# RGB_Video_Controller.net
KiCad netlist of a schematic drawn in Altium Designer
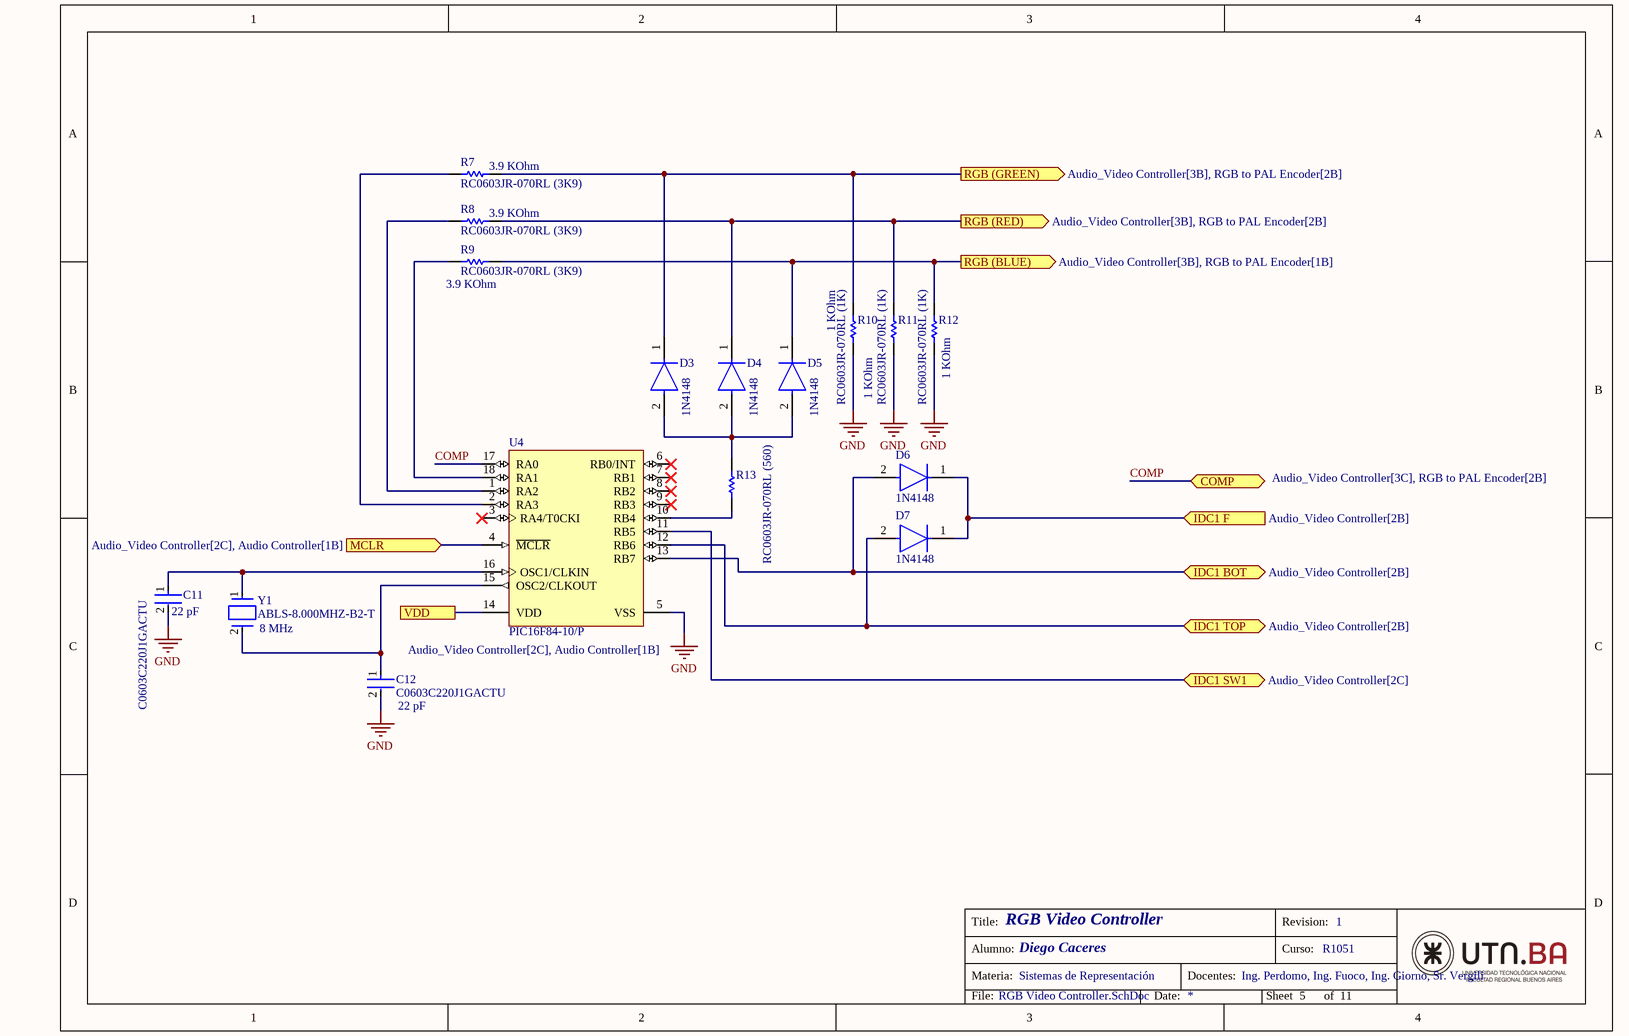
[diagram p0: RGB Video Controller.SchDoc]

(export (version "E")
  (design (tool "Eeschema 10.0.6"))
  (components
    (comp (ref "C11")
      (value "C0603C220J1GACTU")
      (footprint "FP-C0603C-CF-MFG")
      (description "CAP CER 22PF 100V 5% NP0 0603")
      (fields
        (field (name "ALTIUM_VALUE") "22 pF")
        (field (name "MANUFACTURER") "KEMET")
        (field (name "TOLERANCE") "0.05")
      )
      (libsource (lib "Altium Content Vault") (part "b4654b650e69147ec39a6b967a45e02"))
    )
    (comp (ref "C12")
      (value "C0603C220J1GACTU")
      (footprint "FP-C0603C-CF-MFG")
      (description "CAP CER 22PF 100V 5% NP0 0603")
      (fields
        (field (name "ALTIUM_VALUE") "22 pF")
        (field (name "MANUFACTURER") "KEMET")
        (field (name "TOLERANCE") "0.05")
      )
      (libsource (lib "Altium Content Vault") (part "b4654b650e69147ec39a6b967a45e02"))
    )
    (comp (ref "D3")
      (value "1N4148")
      (footprint "FP-017AG-MFG")
      (description "DIODE GEN PURP 100V 200MA DO35")
      (fields (field (name "VOLTAGE") "100V"))
      (libsource (lib "Altium Content Vault") (part "d7152d700b627762746794eb795d46e"))
    )
    (comp (ref "D4")
      (value "1N4148")
      (footprint "FP-017AG-MFG")
      (description "DIODE GEN PURP 100V 200MA DO35")
      (fields (field (name "VOLTAGE") "100V"))
      (libsource (lib "Altium Content Vault") (part "d7152d700b627762746794eb795d46e"))
    )
    (comp (ref "D5")
      (value "1N4148")
      (footprint "FP-017AG-MFG")
      (description "DIODE GEN PURP 100V 200MA DO35")
      (fields (field (name "VOLTAGE") "100V"))
      (libsource (lib "Altium Content Vault") (part "d7152d700b627762746794eb795d46e"))
    )
    (comp (ref "D6")
      (value "1N4148")
      (footprint "FP-017AG-MFG")
      (description "DIODE GEN PURP 100V 200MA DO35")
      (fields (field (name "VOLTAGE") "100V"))
      (libsource (lib "Altium Content Vault") (part "d7152d700b627762746794eb795d46e"))
    )
    (comp (ref "D7")
      (value "1N4148")
      (footprint "FP-017AG-MFG")
      (description "DIODE GEN PURP 100V 200MA DO35")
      (fields (field (name "VOLTAGE") "100V"))
      (libsource (lib "Altium Content Vault") (part "d7152d700b627762746794eb795d46e"))
    )
    (comp (ref "R7")
      (value "RC0603JR-070RL (3K9)")
      (footprint "RESC1608X55X25ML10T15")
      (description "Chip Resistor, 0 Ohm, +/- 5%, 0.1 W, -55 to 155 degC, 0603 (1608 Metric), RoHS, Tape and Reel")
      (fields
        (field (name "TOLERANCE") "5%")
        (field (name "RESISTANCE") "3.9 KOhm")
        (field (name "MANUFACTURER") "Yageo")
      )
      (libsource (lib "Altium Content Vault") (part "RES-2"))
    )
    (comp (ref "R8")
      (value "RC0603JR-070RL (3K9)")
      (footprint "RESC1608X55X25ML10T15")
      (description "Chip Resistor, 0 Ohm, +/- 5%, 0.1 W, -55 to 155 degC, 0603 (1608 Metric), RoHS, Tape and Reel")
      (fields
        (field (name "TOLERANCE") "5%")
        (field (name "RESISTANCE") "3.9 KOhm")
        (field (name "MANUFACTURER") "Yageo")
      )
      (libsource (lib "Altium Content Vault") (part "RES-2"))
    )
    (comp (ref "R9")
      (value "RC0603JR-070RL (3K9)")
      (footprint "RESC1608X55X25ML10T15")
      (description "Chip Resistor, 0 Ohm, +/- 5%, 0.1 W, -55 to 155 degC, 0603 (1608 Metric), RoHS, Tape and Reel")
      (fields
        (field (name "TOLERANCE") "5%")
        (field (name "RESISTANCE") "3.9 KOhm")
        (field (name "MANUFACTURER") "Yageo")
      )
      (libsource (lib "Altium Content Vault") (part "RES-2"))
    )
    (comp (ref "R10")
      (value "RC0603JR-070RL (1K)")
      (footprint "RESC1608X55X25ML10T15")
      (description "Chip Resistor, 0 Ohm, +/- 5%, 0.1 W, -55 to 155 degC, 0603 (1608 Metric), RoHS, Tape and Reel")
      (fields
        (field (name "TOLERANCE") "5%")
        (field (name "RESISTANCE") "1 KOhm")
        (field (name "MANUFACTURER") "Yageo")
      )
      (libsource (lib "Altium Content Vault") (part "RES-2"))
    )
    (comp (ref "R11")
      (value "RC0603JR-070RL (1K)")
      (footprint "RESC1608X55X25ML10T15")
      (description "Chip Resistor, 0 Ohm, +/- 5%, 0.1 W, -55 to 155 degC, 0603 (1608 Metric), RoHS, Tape and Reel")
      (fields
        (field (name "TOLERANCE") "5%")
        (field (name "RESISTANCE") "1 KOhm")
        (field (name "MANUFACTURER") "Yageo")
      )
      (libsource (lib "Altium Content Vault") (part "RES-2"))
    )
    (comp (ref "R12")
      (value "RC0603JR-070RL (1K)")
      (footprint "RESC1608X55X25ML10T15")
      (description "Chip Resistor, 0 Ohm, +/- 5%, 0.1 W, -55 to 155 degC, 0603 (1608 Metric), RoHS, Tape and Reel")
      (fields
        (field (name "TOLERANCE") "5%")
        (field (name "RESISTANCE") "1 KOhm")
        (field (name "MANUFACTURER") "Yageo")
      )
      (libsource (lib "Altium Content Vault") (part "RES-2"))
    )
    (comp (ref "R13")
      (value "RC0603JR-070RL (560)")
      (footprint "RESC1608X55X25ML10T15")
      (description "Chip Resistor, 0 Ohm, +/- 5%, 0.1 W, -55 to 155 degC, 0603 (1608 Metric), RoHS, Tape and Reel")
      (fields (field (name "TOLERANCE") "5%") (field (name "MANUFACTURER") "Yageo"))
      (libsource (lib "Altium Content Vault") (part "RES-2"))
    )
    (comp (ref "U4")
      (value "PIC16F84-10/P")
      (footprint "MCHP-PDIP-P18")
      (description "Flash / EEPROM 8-Bit Microcontroller, 10 MHz, 13 I/O, 0 to 70 degC, 18-pin PDIP (P18), Tube")
      (fields (field (name "MANUFACTURER") "Microchip"))
      (libsource (lib "Altium Content Vault") (part "MCHP-PIC16F83_84-18"))
    )
    (comp (ref "Y1")
      (value "ABLS-8.000MHZ-B2-T")
      (footprint "FP-ABLS-MFG")
      (description "CRYSTAL 8.0000MHZ 18PF SMD")
      (fields (field (name "OPERATING FREQUENCY") "8 MHz") (field (name "TOLERANCE") "20ppm"))
      (libsource (lib "Altium Content Vault") (part "c23a69dc6c9e2f18f2079038eb95dd1"))
    )
  )
  (nets
    (net (code "1") (name "/COMP") (class "Default")
      (node (ref "U4") (pin "17") (pinfunction "RA0_17") (pintype "bidirectional"))
    )
    (net (code "2") (name "/IDC1 BOT") (class "Default")
      (node (ref "D6") (pin "2") (pinfunction "A_2") (pintype "passive"))
      (node (ref "U4") (pin "13") (pinfunction "RB7_13") (pintype "bidirectional"))
    )
    (net (code "3") (name "/IDC1 F") (class "Default")
      (node (ref "D6") (pin "1") (pinfunction "C_1") (pintype "passive"))
      (node (ref "D7") (pin "1") (pinfunction "C_1") (pintype "passive"))
    )
    (net (code "4") (name "/IDC1 SW1") (class "Default")
      (node (ref "U4") (pin "11") (pinfunction "RB5_11") (pintype "bidirectional"))
    )
    (net (code "5") (name "/IDC1 TOP") (class "Default")
      (node (ref "D7") (pin "2") (pinfunction "A_2") (pintype "passive"))
      (node (ref "U4") (pin "12") (pinfunction "RB6_12") (pintype "bidirectional"))
    )
    (net (code "6") (name "/MCLR") (class "Default")
      (node (ref "U4") (pin "4") (pinfunction "~{MCLR}_4") (pintype "input"))
    )
    (net (code "7") (name "/RGB (BLUE)") (class "Default")
      (node (ref "D5") (pin "1") (pinfunction "C_1") (pintype "passive"))
      (node (ref "R12") (pin "1") (pinfunction "1_1") (pintype "passive"))
      (node (ref "R9") (pin "1") (pinfunction "1_1") (pintype "passive"))
    )
    (net (code "8") (name "/RGB (GREEN)") (class "Default")
      (node (ref "D3") (pin "1") (pinfunction "C_1") (pintype "passive"))
      (node (ref "R10") (pin "1") (pinfunction "1_1") (pintype "passive"))
      (node (ref "R7") (pin "1") (pinfunction "1_1") (pintype "passive"))
    )
    (net (code "9") (name "/RGB (RED)") (class "Default")
      (node (ref "D4") (pin "1") (pinfunction "C_1") (pintype "passive"))
      (node (ref "R11") (pin "1") (pinfunction "1_1") (pintype "passive"))
      (node (ref "R8") (pin "1") (pinfunction "1_1") (pintype "passive"))
    )
    (net (code "10") (name "/VDD") (class "Default")
      (node (ref "U4") (pin "14") (pinfunction "VDD_14") (pintype "power_in"))
    )
    (net (code "11") (name "GND") (class "Default")
      (node (ref "C11") (pin "2") (pinfunction "2_2") (pintype "passive"))
      (node (ref "C12") (pin "2") (pinfunction "2_2") (pintype "passive"))
      (node (ref "R10") (pin "2") (pinfunction "2_2") (pintype "passive"))
      (node (ref "R11") (pin "2") (pinfunction "2_2") (pintype "passive"))
      (node (ref "R12") (pin "2") (pinfunction "2_2") (pintype "passive"))
      (node (ref "U4") (pin "5") (pinfunction "VSS_5") (pintype "power_in"))
    )
    (net (code "12") (name "Net-(D3-A)") (class "Default")
      (node (ref "D3") (pin "2") (pinfunction "A_2") (pintype "passive"))
      (node (ref "D4") (pin "2") (pinfunction "A_2") (pintype "passive"))
      (node (ref "D5") (pin "2") (pinfunction "A_2") (pintype "passive"))
      (node (ref "R13") (pin "1") (pinfunction "1_1") (pintype "passive"))
    )
    (net (code "13") (name "Net-(U4-OSC1{slash}CLKIN)") (class "Default")
      (node (ref "C11") (pin "1") (pinfunction "1_1") (pintype "passive"))
      (node (ref "U4") (pin "16") (pinfunction "OSC1/CLKIN_16") (pintype "input"))
      (node (ref "Y1") (pin "1") (pinfunction "1_1") (pintype "passive"))
    )
    (net (code "14") (name "Net-(U4-OSC2{slash}CLKOUT)") (class "Default")
      (node (ref "C12") (pin "1") (pinfunction "1_1") (pintype "passive"))
      (node (ref "U4") (pin "15") (pinfunction "OSC2/CLKOUT_15") (pintype "output"))
      (node (ref "Y1") (pin "2") (pinfunction "2_2") (pintype "passive"))
    )
    (net (code "15") (name "Net-(U4-RA1)") (class "Default")
      (node (ref "R9") (pin "2") (pinfunction "2_2") (pintype "passive"))
      (node (ref "U4") (pin "18") (pinfunction "RA1_18") (pintype "bidirectional"))
    )
    (net (code "16") (name "Net-(U4-RA2)") (class "Default")
      (node (ref "R8") (pin "2") (pinfunction "2_2") (pintype "passive"))
      (node (ref "U4") (pin "1") (pinfunction "RA2_1") (pintype "bidirectional"))
    )
    (net (code "17") (name "Net-(U4-RA3)") (class "Default")
      (node (ref "R7") (pin "2") (pinfunction "2_2") (pintype "passive"))
      (node (ref "U4") (pin "2") (pinfunction "RA3_2") (pintype "bidirectional"))
    )
    (net (code "18") (name "Net-(U4-RB4)") (class "Default")
      (node (ref "R13") (pin "2") (pinfunction "2_2") (pintype "passive"))
      (node (ref "U4") (pin "10") (pinfunction "RB4_10") (pintype "bidirectional"))
    )
    (net (code "19") (name "unconnected-(U4-RA4{slash}T0CKI-Pad3)") (class "Default")
      (node (ref "U4") (pin "3") (pinfunction "RA4/T0CKI_3") (pintype "bidirectional+no_connect"))
    )
    (net (code "20") (name "unconnected-(U4-RB0{slash}INT-Pad6)") (class "Default")
      (node (ref "U4") (pin "6") (pinfunction "RB0/INT_6") (pintype "bidirectional+no_connect"))
    )
    (net (code "21") (name "unconnected-(U4-RB1-Pad7)") (class "Default")
      (node (ref "U4") (pin "7") (pinfunction "RB1_7") (pintype "bidirectional+no_connect"))
    )
    (net (code "22") (name "unconnected-(U4-RB2-Pad8)") (class "Default")
      (node (ref "U4") (pin "8") (pinfunction "RB2_8") (pintype "bidirectional+no_connect"))
    )
    (net (code "23") (name "unconnected-(U4-RB3-Pad9)") (class "Default")
      (node (ref "U4") (pin "9") (pinfunction "RB3_9") (pintype "bidirectional+no_connect"))
    )
  )
)
